# yard-ice-ethernet.net
KiCad netlist of a schematic drawn in Altium Designer
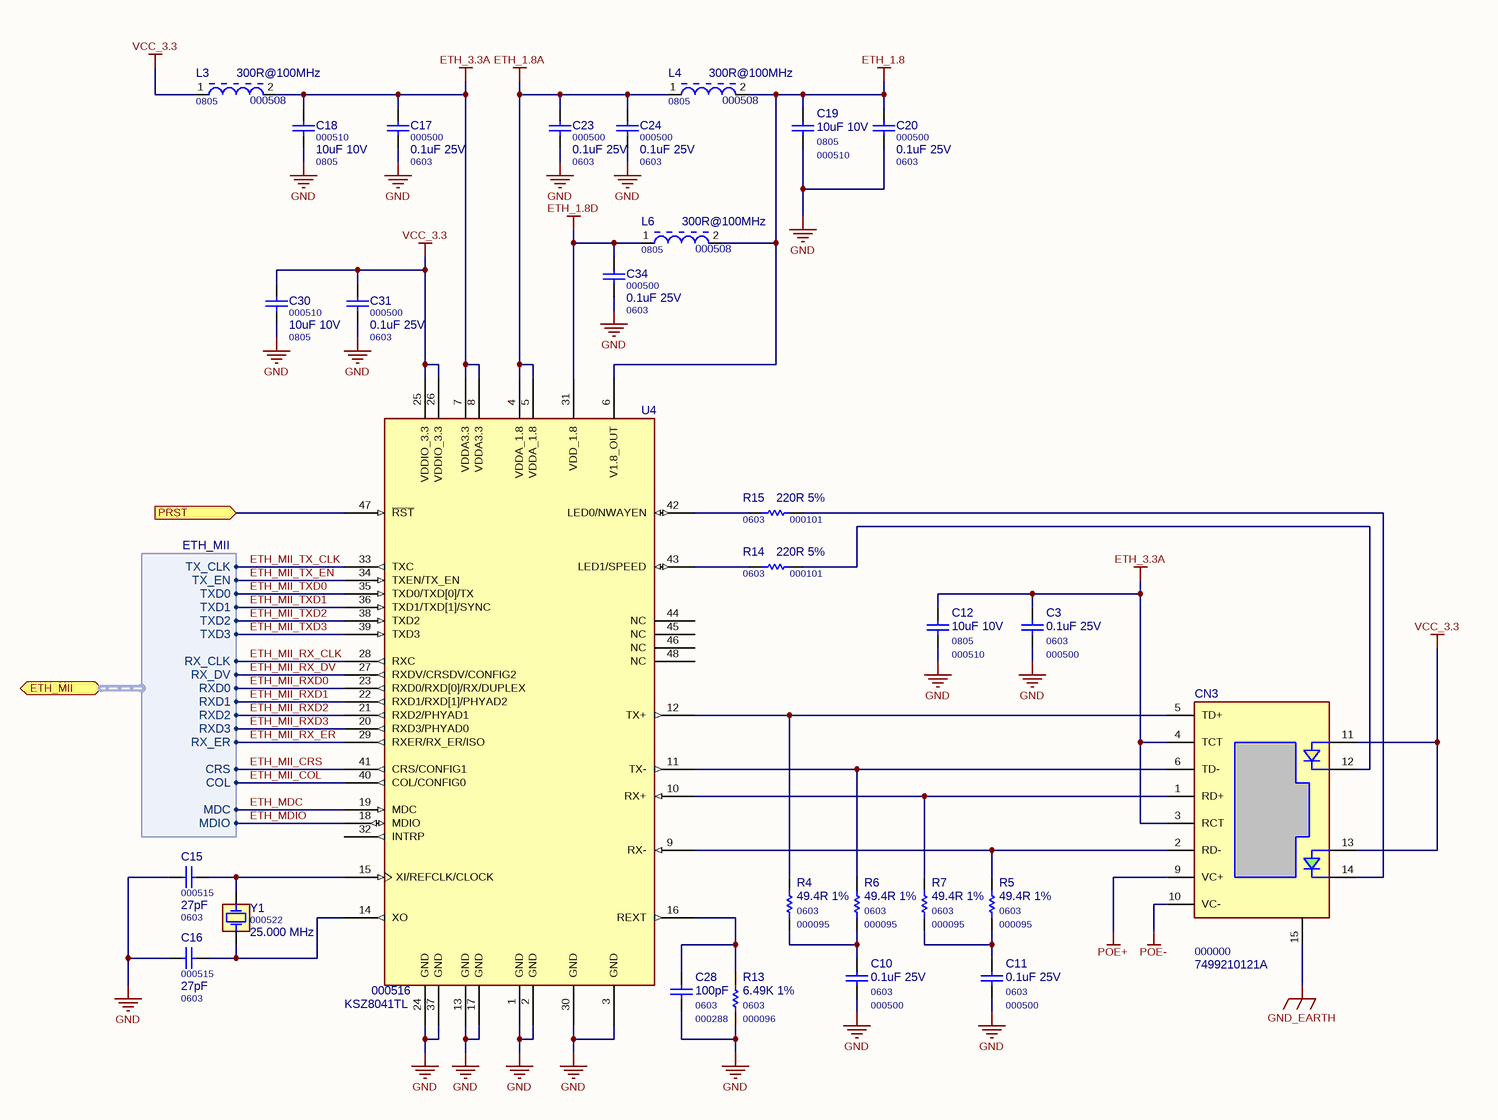
[diagram p0: yard-ice-ethernet.SchDoc]

(export (version "E")
  (design (tool "Eeschema 10.0.6"))
  (components
    (comp (ref "C3")
      (value "000500")
      (footprint "C0603M")
      (description "SMD Ceramic Chip Capacitor - 0603 - X7R")
      (fields
        (field (name "ALTIUM_VALUE") "0.1uF 25V")
        (field (name "PACKAGE") "0603")
        (field (name "MF") "TDK")
      )
      (libsource (lib "discrete-sm") (part "C0603"))
    )
    (comp (ref "C10")
      (value "000500")
      (footprint "C0603M")
      (description "SMD Ceramic Chip Capacitor - 0603 - X7R")
      (fields
        (field (name "ALTIUM_VALUE") "0.1uF 25V")
        (field (name "PACKAGE") "0603")
        (field (name "MF") "TDK")
      )
      (libsource (lib "discrete-sm") (part "C0603"))
    )
    (comp (ref "C11")
      (value "000500")
      (footprint "C0603M")
      (description "SMD Ceramic Chip Capacitor - 0603 - X7R")
      (fields
        (field (name "ALTIUM_VALUE") "0.1uF 25V")
        (field (name "PACKAGE") "0603")
        (field (name "MF") "TDK")
      )
      (libsource (lib "discrete-sm") (part "C0603"))
    )
    (comp (ref "C12")
      (value "000510")
      (footprint "C0805M")
      (description "SMD Ceramic Chip Capacitor - 0805 - X7R")
      (fields
        (field (name "ALTIUM_VALUE") "10uF 10V")
        (field (name "PACKAGE") "0805")
        (field (name "MF") "TDK")
      )
      (libsource (lib "discrete-sm") (part "C0805"))
    )
    (comp (ref "C15")
      (value "000515")
      (footprint "C0603M")
      (description "SMD Ceramic Chip Capacitor - 0603")
      (fields (field (name "ALTIUM_VALUE") "27pF") (field (name "PACKAGE") "0603"))
      (libsource (lib "discrete-sm") (part "C0603"))
    )
    (comp (ref "C16")
      (value "000515")
      (footprint "C0603M")
      (description "SMD Ceramic Chip Capacitor - 0603")
      (fields (field (name "ALTIUM_VALUE") "27pF") (field (name "PACKAGE") "0603"))
      (libsource (lib "discrete-sm") (part "C0603"))
    )
    (comp (ref "C17")
      (value "000500")
      (footprint "C0603M")
      (description "SMD Ceramic Chip Capacitor - 0603 - X7R")
      (fields
        (field (name "ALTIUM_VALUE") "0.1uF 25V")
        (field (name "PACKAGE") "0603")
        (field (name "MF") "TDK")
      )
      (libsource (lib "discrete-sm") (part "C0603"))
    )
    (comp (ref "C18")
      (value "000510")
      (footprint "C0805M")
      (description "SMD Ceramic Chip Capacitor - 0805 - X7R")
      (fields
        (field (name "ALTIUM_VALUE") "10uF 10V")
        (field (name "PACKAGE") "0805")
        (field (name "MF") "TDK")
      )
      (libsource (lib "discrete-sm") (part "C0805"))
    )
    (comp (ref "C19")
      (value "000510")
      (footprint "C0805M")
      (description "SMD Ceramic Chip Capacitor - 0805 - X7R")
      (fields
        (field (name "ALTIUM_VALUE") "10uF 10V")
        (field (name "PACKAGE") "0805")
        (field (name "MF") "TDK")
      )
      (libsource (lib "discrete-sm") (part "C0805"))
    )
    (comp (ref "C20")
      (value "000500")
      (footprint "C0603M")
      (description "SMD Ceramic Chip Capacitor - 0603 - X7R")
      (fields
        (field (name "ALTIUM_VALUE") "0.1uF 25V")
        (field (name "PACKAGE") "0603")
        (field (name "MF") "TDK")
      )
      (libsource (lib "discrete-sm") (part "C0603"))
    )
    (comp (ref "C23")
      (value "000500")
      (footprint "C0603M")
      (description "SMD Ceramic Chip Capacitor - 0603 - X7R")
      (fields
        (field (name "ALTIUM_VALUE") "0.1uF 25V")
        (field (name "PACKAGE") "0603")
        (field (name "MF") "TDK")
      )
      (libsource (lib "discrete-sm") (part "C0603"))
    )
    (comp (ref "C24")
      (value "000500")
      (footprint "C0603M")
      (description "SMD Ceramic Chip Capacitor - 0603 - X7R")
      (fields
        (field (name "ALTIUM_VALUE") "0.1uF 25V")
        (field (name "PACKAGE") "0603")
        (field (name "MF") "TDK")
      )
      (libsource (lib "discrete-sm") (part "C0603"))
    )
    (comp (ref "C28")
      (value "000288")
      (footprint "C0603M")
      (description "SMD Ceramic Chip Capacitor - 0603")
      (fields (field (name "ALTIUM_VALUE") "100pF") (field (name "PACKAGE") "0603"))
      (libsource (lib "discrete-sm") (part "C0603"))
    )
    (comp (ref "C30")
      (value "000510")
      (footprint "C0805M")
      (description "SMD Ceramic Chip Capacitor - 0805 - X7R")
      (fields
        (field (name "ALTIUM_VALUE") "10uF 10V")
        (field (name "PACKAGE") "0805")
        (field (name "MF") "TDK")
      )
      (libsource (lib "discrete-sm") (part "C0805"))
    )
    (comp (ref "C31")
      (value "000500")
      (footprint "C0603M")
      (description "SMD Ceramic Chip Capacitor - 0603 - X7R")
      (fields
        (field (name "ALTIUM_VALUE") "0.1uF 25V")
        (field (name "PACKAGE") "0603")
        (field (name "MF") "TDK")
      )
      (libsource (lib "discrete-sm") (part "C0603"))
    )
    (comp (ref "C34")
      (value "000500")
      (footprint "C0603M")
      (description "SMD Ceramic Chip Capacitor - 0603 - X7R")
      (fields
        (field (name "ALTIUM_VALUE") "0.1uF 25V")
        (field (name "PACKAGE") "0603")
        (field (name "MF") "TDK")
      )
      (libsource (lib "discrete-sm") (part "C0603"))
    )
    (comp (ref "CN3")
      (value "000000")
      (footprint "7499210121A")
      (description "10/100Base-TX PoE RJ45")
      (fields (field (name "MF") "Wurth") (field (name "ALTIUM_VALUE") "7499210121A"))
      (libsource (lib "wurth") (part "7499210121A"))
    )
    (comp (ref "L3")
      (value "000508")
      (footprint "L0805M")
      (description "SMD Ferrite Bead 0805")
      (fields
        (field (name "ALTIUM_VALUE") "300R@100MHz")
        (field (name "PACKAGE") "0805")
        (field (name "MF") "TDK")
      )
      (libsource (lib "discrete-sm") (part "L0805"))
    )
    (comp (ref "L4")
      (value "000508")
      (footprint "L0805M")
      (description "SMD Ferrite Bead 0805")
      (fields
        (field (name "ALTIUM_VALUE") "300R@100MHz")
        (field (name "PACKAGE") "0805")
        (field (name "MF") "TDK")
      )
      (libsource (lib "discrete-sm") (part "L0805"))
    )
    (comp (ref "L6")
      (value "000508")
      (footprint "L0805M")
      (description "SMD Ferrite Bead 0805")
      (fields
        (field (name "ALTIUM_VALUE") "300R@100MHz")
        (field (name "PACKAGE") "0805")
        (field (name "MF") "TDK")
      )
      (libsource (lib "discrete-sm") (part "L0805"))
    )
    (comp (ref "R4")
      (value "000095")
      (footprint "R0603M")
      (description "SMD Chip Resistor - 0603")
      (fields (field (name "ALTIUM_VALUE") "49.4R 1%") (field (name "PACKAGE") "0603"))
      (libsource (lib "discrete-sm") (part "R0603"))
    )
    (comp (ref "R5")
      (value "000095")
      (footprint "R0603M")
      (description "SMD Chip Resistor - 0603")
      (fields (field (name "ALTIUM_VALUE") "49.4R 1%") (field (name "PACKAGE") "0603"))
      (libsource (lib "discrete-sm") (part "R0603"))
    )
    (comp (ref "R6")
      (value "000095")
      (footprint "R0603M")
      (description "SMD Chip Resistor - 0603")
      (fields (field (name "ALTIUM_VALUE") "49.4R 1%") (field (name "PACKAGE") "0603"))
      (libsource (lib "discrete-sm") (part "R0603"))
    )
    (comp (ref "R7")
      (value "000095")
      (footprint "R0603M")
      (description "SMD Chip Resistor - 0603")
      (fields (field (name "ALTIUM_VALUE") "49.4R 1%") (field (name "PACKAGE") "0603"))
      (libsource (lib "discrete-sm") (part "R0603"))
    )
    (comp (ref "R13")
      (value "000096")
      (footprint "R0603M")
      (description "SMD Chip Resistor - 0603")
      (fields (field (name "ALTIUM_VALUE") "6.49K 1%") (field (name "PACKAGE") "0603"))
      (libsource (lib "discrete-sm") (part "R0603"))
    )
    (comp (ref "R14")
      (value "000101")
      (footprint "R0603M")
      (description "SMD Chip Resistor - 0603")
      (fields (field (name "ALTIUM_VALUE") "220R 5%") (field (name "PACKAGE") "0603"))
      (libsource (lib "discrete-sm") (part "R0603"))
    )
    (comp (ref "R15")
      (value "000101")
      (footprint "R0603M")
      (description "SMD Chip Resistor - 0603")
      (fields (field (name "ALTIUM_VALUE") "220R 5%") (field (name "PACKAGE") "0603"))
      (libsource (lib "discrete-sm") (part "R0603"))
    )
    (comp (ref "U4")
      (value "000516")
      (footprint "48-TQFP")
      (description "10Base-T/100Base-TX Physical Layer Transceiver")
      (fields (field (name "ALTIUM_VALUE") "KSZ8041TL") (field (name "MF") "Micrel"))
      (libsource (lib "micrel-ethernet") (part "KSZ8041TL"))
    )
    (comp (ref "Y1")
      (value "000522")
      (footprint "ABM3-H")
      (description "Miniature Ceramic SMD Crystal")
      (fields (field (name "MF") "Abracon") (field (name "ALTIUM_VALUE") "25.000 MHz"))
      (libsource (lib "abracon") (part "ABM3"))
    )
  )
  (nets
    (net (code "2") (name "/ETH_MDC") (class "Default")
      (node (ref "U4") (pin "19") (pinfunction "MDC_19") (pintype "input"))
    )
    (net (code "3") (name "/ETH_MDIO") (class "Default")
      (node (ref "U4") (pin "18") (pinfunction "MDIO_18") (pintype "bidirectional"))
    )
    (net (code "4") (name "/ETH_MII_COL") (class "Default")
      (node (ref "U4") (pin "40") (pinfunction "COL/CONFIG0_40") (pintype "output"))
    )
    (net (code "5") (name "/ETH_MII_CRS") (class "Default")
      (node (ref "U4") (pin "41") (pinfunction "CRS/CONFIG1_41") (pintype "output"))
    )
    (net (code "6") (name "/ETH_MII_RXD0") (class "Default")
      (node (ref "U4") (pin "23") (pinfunction "RXD0/RXD[0]/RX/DUPLEX_23") (pintype "output"))
    )
    (net (code "7") (name "/ETH_MII_RXD1") (class "Default")
      (node (ref "U4") (pin "22") (pinfunction "RXD1/RXD[1]/PHYAD2_22") (pintype "output"))
    )
    (net (code "8") (name "/ETH_MII_RXD2") (class "Default")
      (node (ref "U4") (pin "21") (pinfunction "RXD2/PHYAD1_21") (pintype "output"))
    )
    (net (code "9") (name "/ETH_MII_RXD3") (class "Default")
      (node (ref "U4") (pin "20") (pinfunction "RXD3/PHYAD0_20") (pintype "output"))
    )
    (net (code "10") (name "/ETH_MII_RX_CLK") (class "Default")
      (node (ref "U4") (pin "28") (pinfunction "RXC_28") (pintype "output"))
    )
    (net (code "11") (name "/ETH_MII_RX_DV") (class "Default")
      (node (ref "U4") (pin "27") (pinfunction "RXDV/CRSDV/CONFIG2_27") (pintype "output"))
    )
    (net (code "12") (name "/ETH_MII_RX_ER") (class "Default")
      (node (ref "U4") (pin "29") (pinfunction "RXER/RX_ER/ISO_29") (pintype "output"))
    )
    (net (code "13") (name "/ETH_MII_TXD0") (class "Default")
      (node (ref "U4") (pin "35") (pinfunction "TXD0/TXD[0]/TX_35") (pintype "input"))
    )
    (net (code "14") (name "/ETH_MII_TXD1") (class "Default")
      (node (ref "U4") (pin "36") (pinfunction "TXD1/TXD[1]/SYNC_36") (pintype "input"))
    )
    (net (code "15") (name "/ETH_MII_TXD2") (class "Default")
      (node (ref "U4") (pin "38") (pinfunction "TXD2_38") (pintype "input"))
    )
    (net (code "16") (name "/ETH_MII_TXD3") (class "Default")
      (node (ref "U4") (pin "39") (pinfunction "TXD3_39") (pintype "input"))
    )
    (net (code "17") (name "/ETH_MII_TX_CLK") (class "Default")
      (node (ref "U4") (pin "33") (pinfunction "TXC_33") (pintype "output"))
    )
    (net (code "18") (name "/ETH_MII_TX_EN") (class "Default")
      (node (ref "U4") (pin "34") (pinfunction "TXEN/TX_EN_34") (pintype "input"))
    )
    (net (code "19") (name "/PRST") (class "Default")
      (node (ref "U4") (pin "47") (pinfunction "~{RST}_47") (pintype "input"))
    )
    (net (code "21") (name "ETH_1.8") (class "Default")
      (node (ref "C19") (pin "1") (pinfunction "1_1") (pintype "passive"))
      (node (ref "C20") (pin "1") (pinfunction "1_1") (pintype "passive"))
      (node (ref "L4") (pin "2") (pinfunction "2_2") (pintype "passive"))
      (node (ref "L6") (pin "2") (pinfunction "2_2") (pintype "passive"))
      (node (ref "U4") (pin "6") (pinfunction "V1.8_OUT_6") (pintype "power_in"))
    )
    (net (code "22") (name "ETH_1.8A") (class "Default")
      (node (ref "C23") (pin "1") (pinfunction "1_1") (pintype "passive"))
      (node (ref "C24") (pin "1") (pinfunction "1_1") (pintype "passive"))
      (node (ref "L4") (pin "1") (pinfunction "1_1") (pintype "passive"))
      (node (ref "U4") (pin "4") (pinfunction "VDDA_1.8_4") (pintype "power_in"))
      (node (ref "U4") (pin "5") (pinfunction "VDDA_1.8_5") (pintype "power_in"))
    )
    (net (code "23") (name "ETH_1.8D") (class "Default")
      (node (ref "C34") (pin "1") (pinfunction "1_1") (pintype "passive"))
      (node (ref "L6") (pin "1") (pinfunction "1_1") (pintype "passive"))
      (node (ref "U4") (pin "31") (pinfunction "VDD_1.8_31") (pintype "power_in"))
    )
    (net (code "24") (name "ETH_3.3A") (class "Default")
      (node (ref "C12") (pin "1") (pinfunction "1_1") (pintype "passive"))
      (node (ref "C17") (pin "1") (pinfunction "1_1") (pintype "passive"))
      (node (ref "C18") (pin "1") (pinfunction "1_1") (pintype "passive"))
      (node (ref "C3") (pin "1") (pinfunction "1_1") (pintype "passive"))
      (node (ref "CN3") (pin "3") (pinfunction "RCT_3") (pintype "passive"))
      (node (ref "CN3") (pin "4") (pinfunction "TCT_4") (pintype "passive"))
      (node (ref "L3") (pin "2") (pinfunction "2_2") (pintype "passive"))
      (node (ref "U4") (pin "7") (pinfunction "VDDA3.3_7") (pintype "power_in"))
      (node (ref "U4") (pin "8") (pinfunction "VDDA3.3_8") (pintype "power_in"))
    )
    (net (code "25") (name "GND") (class "Default")
      (node (ref "C10") (pin "2") (pinfunction "2_2") (pintype "passive"))
      (node (ref "C11") (pin "2") (pinfunction "2_2") (pintype "passive"))
      (node (ref "C12") (pin "2") (pinfunction "2_2") (pintype "passive"))
      (node (ref "C15") (pin "1") (pinfunction "1_1") (pintype "passive"))
      (node (ref "C16") (pin "1") (pinfunction "1_1") (pintype "passive"))
      (node (ref "C17") (pin "2") (pinfunction "2_2") (pintype "passive"))
      (node (ref "C18") (pin "2") (pinfunction "2_2") (pintype "passive"))
      (node (ref "C19") (pin "2") (pinfunction "2_2") (pintype "passive"))
      (node (ref "C20") (pin "2") (pinfunction "2_2") (pintype "passive"))
      (node (ref "C23") (pin "2") (pinfunction "2_2") (pintype "passive"))
      (node (ref "C24") (pin "2") (pinfunction "2_2") (pintype "passive"))
      (node (ref "C28") (pin "2") (pinfunction "2_2") (pintype "passive"))
      (node (ref "C3") (pin "2") (pinfunction "2_2") (pintype "passive"))
      (node (ref "C30") (pin "2") (pinfunction "2_2") (pintype "passive"))
      (node (ref "C31") (pin "2") (pinfunction "2_2") (pintype "passive"))
      (node (ref "C34") (pin "2") (pinfunction "2_2") (pintype "passive"))
      (node (ref "R13") (pin "1") (pinfunction "1_1") (pintype "passive"))
      (node (ref "U4") (pin "1") (pinfunction "GND_1") (pintype "power_in"))
      (node (ref "U4") (pin "13") (pinfunction "GND_13") (pintype "power_in"))
      (node (ref "U4") (pin "17") (pinfunction "GND_17") (pintype "power_in"))
      (node (ref "U4") (pin "2") (pinfunction "GND_2") (pintype "power_in"))
      (node (ref "U4") (pin "24") (pinfunction "GND_24") (pintype "power_in"))
      (node (ref "U4") (pin "3") (pinfunction "GND_3") (pintype "power_in"))
      (node (ref "U4") (pin "30") (pinfunction "GND_30") (pintype "power_in"))
      (node (ref "U4") (pin "37") (pinfunction "GND_37") (pintype "power_in"))
    )
    (net (code "26") (name "GND_EARTH") (class "Default")
      (node (ref "CN3") (pin "15") (pinfunction "SHIELD_15") (pintype "passive"))
    )
    (net (code "27") (name "Net-(C10-Pad1)") (class "Default")
      (node (ref "C10") (pin "1") (pinfunction "1_1") (pintype "passive"))
      (node (ref "R4") (pin "1") (pinfunction "1_1") (pintype "passive"))
      (node (ref "R6") (pin "1") (pinfunction "1_1") (pintype "passive"))
    )
    (net (code "28") (name "Net-(C11-Pad1)") (class "Default")
      (node (ref "C11") (pin "1") (pinfunction "1_1") (pintype "passive"))
      (node (ref "R5") (pin "1") (pinfunction "1_1") (pintype "passive"))
      (node (ref "R7") (pin "1") (pinfunction "1_1") (pintype "passive"))
    )
    (net (code "29") (name "Net-(CN3-K1)") (class "Default")
      (node (ref "CN3") (pin "14") (pinfunction "K1_14") (pintype "passive"))
      (node (ref "R15") (pin "1") (pinfunction "1_1") (pintype "passive"))
    )
    (net (code "30") (name "Net-(CN3-K2)") (class "Default")
      (node (ref "CN3") (pin "12") (pinfunction "K2_12") (pintype "passive"))
      (node (ref "R14") (pin "1") (pinfunction "1_1") (pintype "passive"))
    )
    (net (code "31") (name "Net-(CN3-RD+)") (class "Default")
      (node (ref "CN3") (pin "1") (pinfunction "RD+_1") (pintype "passive"))
      (node (ref "R7") (pin "2") (pinfunction "2_2") (pintype "passive"))
      (node (ref "U4") (pin "10") (pinfunction "RX+_10") (pintype "input"))
    )
    (net (code "32") (name "Net-(CN3-RD-)") (class "Default")
      (node (ref "CN3") (pin "2") (pinfunction "RD-_2") (pintype "passive"))
      (node (ref "R5") (pin "2") (pinfunction "2_2") (pintype "passive"))
      (node (ref "U4") (pin "9") (pinfunction "RX-_9") (pintype "input"))
    )
    (net (code "33") (name "Net-(CN3-TD+)") (class "Default")
      (node (ref "CN3") (pin "5") (pinfunction "TD+_5") (pintype "passive"))
      (node (ref "R4") (pin "2") (pinfunction "2_2") (pintype "passive"))
      (node (ref "U4") (pin "12") (pinfunction "TX+_12") (pintype "output"))
    )
    (net (code "34") (name "Net-(CN3-TD-)") (class "Default")
      (node (ref "CN3") (pin "6") (pinfunction "TD-_6") (pintype "passive"))
      (node (ref "R6") (pin "2") (pinfunction "2_2") (pintype "passive"))
      (node (ref "U4") (pin "11") (pinfunction "TX-_11") (pintype "output"))
    )
    (net (code "35") (name "Net-(U4-LED0{slash}NWAYEN)") (class "Default")
      (node (ref "R15") (pin "2") (pinfunction "2_2") (pintype "passive"))
      (node (ref "U4") (pin "42") (pinfunction "LED0/NWAYEN_42") (pintype "bidirectional"))
    )
    (net (code "36") (name "Net-(U4-LED1{slash}SPEED)") (class "Default")
      (node (ref "R14") (pin "2") (pinfunction "2_2") (pintype "passive"))
      (node (ref "U4") (pin "43") (pinfunction "LED1/SPEED_43") (pintype "bidirectional"))
    )
    (net (code "37") (name "Net-(U4-REXT)") (class "Default")
      (node (ref "C28") (pin "1") (pinfunction "1_1") (pintype "passive"))
      (node (ref "R13") (pin "2") (pinfunction "2_2") (pintype "passive"))
      (node (ref "U4") (pin "16") (pinfunction "REXT_16") (pintype "output"))
    )
    (net (code "38") (name "Net-(U4-XI{slash}REFCLK{slash}CLOCK)") (class "Default")
      (node (ref "C15") (pin "2") (pinfunction "2_2") (pintype "passive"))
      (node (ref "U4") (pin "15") (pinfunction "XI/REFCLK/CLOCK_15") (pintype "input"))
      (node (ref "Y1") (pin "1") (pinfunction "1_1") (pintype "passive"))
    )
    (net (code "39") (name "Net-(U4-XO)") (class "Default")
      (node (ref "C16") (pin "2") (pinfunction "2_2") (pintype "passive"))
      (node (ref "U4") (pin "14") (pinfunction "XO_14") (pintype "output"))
      (node (ref "Y1") (pin "2") (pinfunction "2_2") (pintype "passive"))
    )
    (net (code "40") (name "POE+") (class "Default")
      (node (ref "CN3") (pin "9") (pinfunction "VC+_9") (pintype "passive"))
    )
    (net (code "41") (name "POE-") (class "Default")
      (node (ref "CN3") (pin "10") (pinfunction "VC-_10") (pintype "passive"))
    )
    (net (code "42") (name "VCC_3.3") (class "Default")
      (node (ref "C30") (pin "1") (pinfunction "1_1") (pintype "passive"))
      (node (ref "C31") (pin "1") (pinfunction "1_1") (pintype "passive"))
      (node (ref "CN3") (pin "11") (pinfunction "A2_11") (pintype "passive"))
      (node (ref "CN3") (pin "13") (pinfunction "A1_13") (pintype "passive"))
      (node (ref "L3") (pin "1") (pinfunction "1_1") (pintype "passive"))
      (node (ref "U4") (pin "25") (pinfunction "VDDIO_3.3_25") (pintype "power_in"))
      (node (ref "U4") (pin "26") (pinfunction "VDDIO_3.3_26") (pintype "power_in"))
    )
    (net (code "43") (name "unconnected-(U4-INTRP-Pad32)") (class "Default")
      (node (ref "U4") (pin "32") (pinfunction "INTRP_32") (pintype "output"))
    )
    (net (code "44") (name "unconnected-(U4-NC-Pad44)") (class "Default")
      (node (ref "U4") (pin "44") (pinfunction "NC_44") (pintype "passive"))
    )
    (net (code "45") (name "unconnected-(U4-NC-Pad45)") (class "Default")
      (node (ref "U4") (pin "45") (pinfunction "NC_45") (pintype "passive"))
    )
    (net (code "46") (name "unconnected-(U4-NC-Pad46)") (class "Default")
      (node (ref "U4") (pin "46") (pinfunction "NC_46") (pintype "passive"))
    )
    (net (code "47") (name "unconnected-(U4-NC-Pad48)") (class "Default")
      (node (ref "U4") (pin "48") (pinfunction "NC_48") (pintype "passive"))
    )
  )
)
